# Mezclador2.net
KiCad netlist of a schematic drawn in Altium Designer
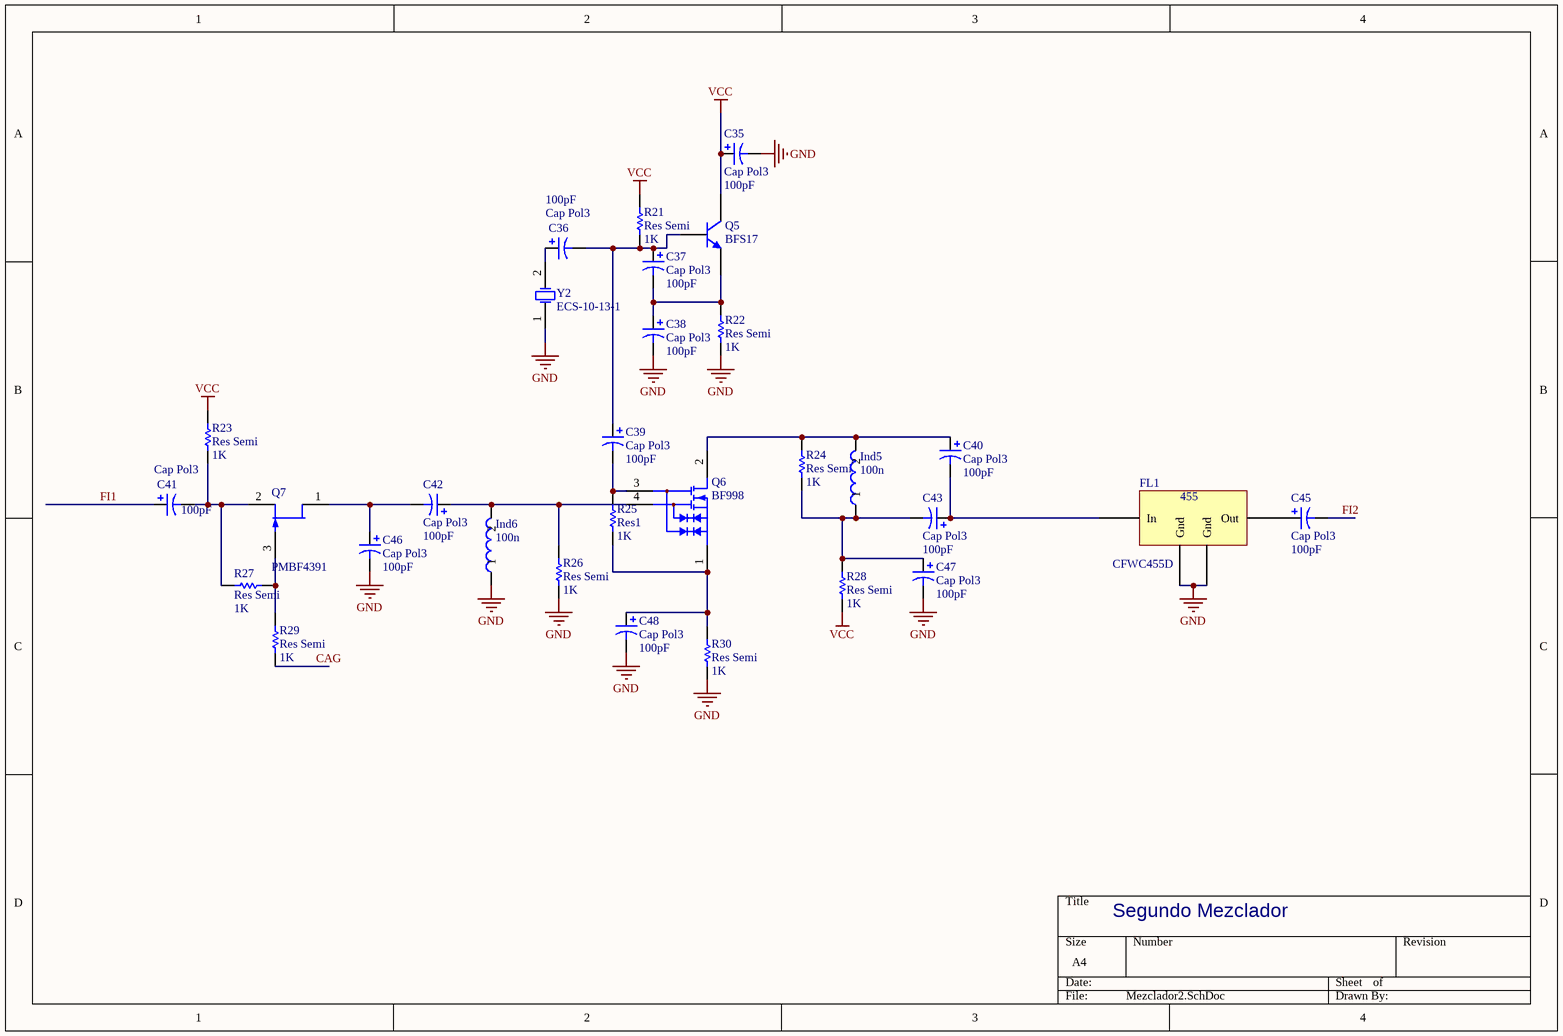
[diagram p0: Mezclador2.SchDoc]

(export (version "E")
  (design (tool "Eeschema 10.0.6"))
  (components
    (comp (ref "C35")
      (value "Cap Pol3")
      (footprint "C0805")
      (description "Polarized Capacitor (Surface Mount)")
      (fields (field (name "ALTIUM_VALUE") "100pF") (field (name "PUBLISHER") "Altium Limited"))
      (libsource (lib "Miscellaneous Devices") (part "Cap Pol3"))
    )
    (comp (ref "C36")
      (value "Cap Pol3")
      (footprint "C0805")
      (description "Polarized Capacitor (Surface Mount)")
      (fields (field (name "ALTIUM_VALUE") "100pF") (field (name "PUBLISHER") "Altium Limited"))
      (libsource (lib "Miscellaneous Devices") (part "Cap Pol3"))
    )
    (comp (ref "C37")
      (value "Cap Pol3")
      (footprint "C0805")
      (description "Polarized Capacitor (Surface Mount)")
      (fields (field (name "ALTIUM_VALUE") "100pF") (field (name "PUBLISHER") "Altium Limited"))
      (libsource (lib "Miscellaneous Devices") (part "Cap Pol3"))
    )
    (comp (ref "C38")
      (value "Cap Pol3")
      (footprint "C0805")
      (description "Polarized Capacitor (Surface Mount)")
      (fields (field (name "ALTIUM_VALUE") "100pF") (field (name "PUBLISHER") "Altium Limited"))
      (libsource (lib "Miscellaneous Devices") (part "Cap Pol3"))
    )
    (comp (ref "C39")
      (value "Cap Pol3")
      (footprint "C0805")
      (description "Polarized Capacitor (Surface Mount)")
      (fields (field (name "ALTIUM_VALUE") "100pF") (field (name "PUBLISHER") "Altium Limited"))
      (libsource (lib "Miscellaneous Devices") (part "Cap Pol3"))
    )
    (comp (ref "C40")
      (value "Cap Pol3")
      (footprint "C0805")
      (description "Polarized Capacitor (Surface Mount)")
      (fields (field (name "ALTIUM_VALUE") "100pF") (field (name "PUBLISHER") "Altium Limited"))
      (libsource (lib "Miscellaneous Devices") (part "Cap Pol3"))
    )
    (comp (ref "C41")
      (value "Cap Pol3")
      (footprint "C0805")
      (description "Polarized Capacitor (Surface Mount)")
      (fields (field (name "ALTIUM_VALUE") "100pF") (field (name "PUBLISHER") "Altium Limited"))
      (libsource (lib "Miscellaneous Devices") (part "Cap Pol3"))
    )
    (comp (ref "C42")
      (value "Cap Pol3")
      (footprint "C0805")
      (description "Polarized Capacitor (Surface Mount)")
      (fields (field (name "ALTIUM_VALUE") "100pF") (field (name "PUBLISHER") "Altium Limited"))
      (libsource (lib "Miscellaneous Devices") (part "Cap Pol3"))
    )
    (comp (ref "C43")
      (value "Cap Pol3")
      (footprint "C0805")
      (description "Polarized Capacitor (Surface Mount)")
      (fields (field (name "ALTIUM_VALUE") "100pF") (field (name "PUBLISHER") "Altium Limited"))
      (libsource (lib "Miscellaneous Devices") (part "Cap Pol3"))
    )
    (comp (ref "C45")
      (value "Cap Pol3")
      (footprint "C0805")
      (description "Polarized Capacitor (Surface Mount)")
      (fields (field (name "ALTIUM_VALUE") "100pF") (field (name "PUBLISHER") "Altium Limited"))
      (libsource (lib "Miscellaneous Devices") (part "Cap Pol3"))
    )
    (comp (ref "C46")
      (value "Cap Pol3")
      (footprint "C0805")
      (description "Polarized Capacitor (Surface Mount)")
      (fields (field (name "ALTIUM_VALUE") "100pF") (field (name "PUBLISHER") "Altium Limited"))
      (libsource (lib "Miscellaneous Devices") (part "Cap Pol3"))
    )
    (comp (ref "C47")
      (value "Cap Pol3")
      (footprint "C0805")
      (description "Polarized Capacitor (Surface Mount)")
      (fields (field (name "ALTIUM_VALUE") "100pF") (field (name "PUBLISHER") "Altium Limited"))
      (libsource (lib "Miscellaneous Devices") (part "Cap Pol3"))
    )
    (comp (ref "C48")
      (value "Cap Pol3")
      (footprint "C0805")
      (description "Polarized Capacitor (Surface Mount)")
      (fields (field (name "ALTIUM_VALUE") "100pF") (field (name "PUBLISHER") "Altium Limited"))
      (libsource (lib "Miscellaneous Devices") (part "Cap Pol3"))
    )
    (comp (ref "FL1")
      (value "CFWC455D")
      (footprint "CFWC455")
      (description "Filtro ceramico")
      (libsource (lib "epf") (part "CFWC455D3"))
    )
    (comp (ref "Ind5")
      (value "Ind2")
      (footprint "AXIAL-0.3")
      (fields (field (name "VALOR") "100n"))
      (libsource (lib "epf") (part "Ind2"))
    )
    (comp (ref "Ind6")
      (value "Ind2")
      (footprint "AXIAL-0.3")
      (fields (field (name "VALOR") "100n"))
      (libsource (lib "epf") (part "Ind2"))
    )
    (comp (ref "Q5")
      (value "BFS17")
      (footprint "SOT-23")
      (description "NPN 1 GHz Wideband Transistor")
      (fields (field (name "PUBLISHER") "Altium Limited"))
      (libsource (lib "Philips Discrete BJT - RF Transistor") (part "BFS17"))
    )
    (comp (ref "Q6")
      (value "BF998")
      (footprint "SOT-143")
      (description "Silicon N-channel Dual-gate MOSFET")
      (fields (field (name "PUBLISHER") "Altium Limited"))
      (libsource (lib "Philips Discrete MOSFET - Low Power") (part "BF998"))
    )
    (comp (ref "Q7")
      (value "PMBF4391")
      (footprint "SOT23_N")
      (description "N-channel Silicon Junction Field-effect Transistor")
      (fields (field (name "PUBLISHER") "Altium Limited"))
      (libsource (lib "Philips Discrete JFET") (part "PMBF4391"))
    )
    (comp (ref "R21")
      (value "Res Semi")
      (footprint "2012[0805]")
      (description "Semiconductor Resistor")
      (fields (field (name "ALTIUM_VALUE") "1K") (field (name "PUBLISHER") "Altium Limited"))
      (libsource (lib "Miscellaneous Devices") (part "Res Semi"))
    )
    (comp (ref "R22")
      (value "Res Semi")
      (footprint "2012[0805]")
      (description "Semiconductor Resistor")
      (fields (field (name "ALTIUM_VALUE") "1K") (field (name "PUBLISHER") "Altium Limited"))
      (libsource (lib "Miscellaneous Devices") (part "Res Semi"))
    )
    (comp (ref "R23")
      (value "Res Semi")
      (footprint "2012[0805]")
      (description "Semiconductor Resistor")
      (fields (field (name "ALTIUM_VALUE") "1K") (field (name "PUBLISHER") "Altium Limited"))
      (libsource (lib "Miscellaneous Devices") (part "Res Semi"))
    )
    (comp (ref "R24")
      (value "Res Semi")
      (footprint "2012[0805]")
      (description "Semiconductor Resistor")
      (fields (field (name "ALTIUM_VALUE") "1K") (field (name "PUBLISHER") "Altium Limited"))
      (libsource (lib "Miscellaneous Devices") (part "Res Semi"))
    )
    (comp (ref "R25")
      (value "Res1")
      (footprint "AXIAL-0.3")
      (description "Resistor")
      (fields (field (name "ALTIUM_VALUE") "1K") (field (name "PUBLISHER") "Altium Limited"))
      (libsource (lib "Miscellaneous Devices") (part "Res1"))
    )
    (comp (ref "R26")
      (value "Res Semi")
      (footprint "2012[0805]")
      (description "Semiconductor Resistor")
      (fields (field (name "ALTIUM_VALUE") "1K") (field (name "PUBLISHER") "Altium Limited"))
      (libsource (lib "Miscellaneous Devices") (part "Res Semi"))
    )
    (comp (ref "R27")
      (value "Res Semi")
      (footprint "2012[0805]")
      (description "Semiconductor Resistor")
      (fields (field (name "ALTIUM_VALUE") "1K") (field (name "PUBLISHER") "Altium Limited"))
      (libsource (lib "Miscellaneous Devices") (part "Res Semi"))
    )
    (comp (ref "R28")
      (value "Res Semi")
      (footprint "2012[0805]")
      (description "Semiconductor Resistor")
      (fields (field (name "ALTIUM_VALUE") "1K") (field (name "PUBLISHER") "Altium Limited"))
      (libsource (lib "Miscellaneous Devices") (part "Res Semi"))
    )
    (comp (ref "R29")
      (value "Res Semi")
      (footprint "2012[0805]")
      (description "Semiconductor Resistor")
      (fields (field (name "ALTIUM_VALUE") "1K") (field (name "PUBLISHER") "Altium Limited"))
      (libsource (lib "Miscellaneous Devices") (part "Res Semi"))
    )
    (comp (ref "R30")
      (value "Res Semi")
      (footprint "2012[0805]")
      (description "Semiconductor Resistor")
      (fields (field (name "ALTIUM_VALUE") "1K") (field (name "PUBLISHER") "Altium Limited"))
      (libsource (lib "Miscellaneous Devices") (part "Res Semi"))
    )
    (comp (ref "Y2")
      (value "ECS-10-13-1")
      (footprint "HC-49U")
      (description "Crystal Oscillator")
      (fields (field (name "PUBLISHER") "Altium Limited"))
      (libsource (lib "ECS Crystal Oscillator") (part "ECS-10-13-1"))
    )
  )
  (nets
    (net (code "1") (name "/CAG") (class "Default")
      (node (ref "R29") (pin "2") (pinfunction "2_2") (pintype "passive"))
    )
    (net (code "2") (name "/FI1") (class "Default")
      (node (ref "C41") (pin "1") (pinfunction "1_1") (pintype "passive"))
    )
    (net (code "3") (name "/FI2") (class "Default")
      (node (ref "C45") (pin "2") (pinfunction "2_2") (pintype "passive"))
    )
    (net (code "4") (name "GND") (class "Default")
      (node (ref "C35") (pin "2") (pinfunction "2_2") (pintype "passive"))
      (node (ref "C38") (pin "2") (pinfunction "2_2") (pintype "passive"))
      (node (ref "C46") (pin "2") (pinfunction "2_2") (pintype "passive"))
      (node (ref "C47") (pin "2") (pinfunction "2_2") (pintype "passive"))
      (node (ref "C48") (pin "2") (pinfunction "2_2") (pintype "passive"))
      (node (ref "FL1") (pin "3") (pinfunction "Gnd_3") (pintype "passive"))
      (node (ref "FL1") (pin "4") (pinfunction "Gnd_4") (pintype "passive"))
      (node (ref "Ind6") (pin "1") (pinfunction "1_1") (pintype "passive"))
      (node (ref "R22") (pin "1") (pinfunction "1_1") (pintype "passive"))
      (node (ref "R26") (pin "1") (pinfunction "1_1") (pintype "passive"))
      (node (ref "R30") (pin "1") (pinfunction "1_1") (pintype "passive"))
      (node (ref "Y2") (pin "1") (pinfunction "OSC1_1") (pintype "passive"))
    )
    (net (code "5") (name "Net-(C43-Pad2)") (class "Default")
      (node (ref "C43") (pin "2") (pinfunction "2_2") (pintype "passive"))
      (node (ref "C47") (pin "1") (pinfunction "1_1") (pintype "passive"))
      (node (ref "Ind5") (pin "1") (pinfunction "1_1") (pintype "passive"))
      (node (ref "R24") (pin "1") (pinfunction "1_1") (pintype "passive"))
      (node (ref "R28") (pin "2") (pinfunction "2_2") (pintype "passive"))
    )
    (net (code "6") (name "Net-(FL1-In)") (class "Default")
      (node (ref "C40") (pin "2") (pinfunction "2_2") (pintype "passive"))
      (node (ref "C43") (pin "1") (pinfunction "1_1") (pintype "passive"))
      (node (ref "FL1") (pin "1") (pinfunction "In_1") (pintype "passive"))
    )
    (net (code "7") (name "Net-(FL1-Out)") (class "Default")
      (node (ref "C45") (pin "1") (pinfunction "1_1") (pintype "passive"))
      (node (ref "FL1") (pin "2") (pinfunction "Out_2") (pintype "passive"))
    )
    (net (code "8") (name "Net-(Q5-B)") (class "Default")
      (node (ref "C36") (pin "2") (pinfunction "2_2") (pintype "passive"))
      (node (ref "C37") (pin "1") (pinfunction "1_1") (pintype "passive"))
      (node (ref "C39") (pin "1") (pinfunction "1_1") (pintype "passive"))
      (node (ref "Q5") (pin "1") (pinfunction "B_1") (pintype "passive"))
      (node (ref "R21") (pin "1") (pinfunction "1_1") (pintype "passive"))
    )
    (net (code "9") (name "Net-(Q5-E)") (class "Default")
      (node (ref "C37") (pin "2") (pinfunction "2_2") (pintype "passive"))
      (node (ref "C38") (pin "1") (pinfunction "1_1") (pintype "passive"))
      (node (ref "Q5") (pin "2") (pinfunction "E_2") (pintype "passive"))
      (node (ref "R22") (pin "2") (pinfunction "2_2") (pintype "passive"))
    )
    (net (code "10") (name "Net-(Q6-D)") (class "Default")
      (node (ref "C40") (pin "1") (pinfunction "1_1") (pintype "passive"))
      (node (ref "Ind5") (pin "2") (pinfunction "2_2") (pintype "passive"))
      (node (ref "Q6") (pin "2") (pinfunction "D_2") (pintype "passive"))
      (node (ref "R24") (pin "2") (pinfunction "2_2") (pintype "passive"))
    )
    (net (code "11") (name "Net-(Q6-G1)") (class "Default")
      (node (ref "C42") (pin "1") (pinfunction "1_1") (pintype "passive"))
      (node (ref "Ind6") (pin "2") (pinfunction "2_2") (pintype "passive"))
      (node (ref "Q6") (pin "4") (pinfunction "G1_4") (pintype "passive"))
      (node (ref "R26") (pin "2") (pinfunction "2_2") (pintype "passive"))
    )
    (net (code "12") (name "Net-(Q6-G2)") (class "Default")
      (node (ref "C39") (pin "2") (pinfunction "2_2") (pintype "passive"))
      (node (ref "Q6") (pin "3") (pinfunction "G2_3") (pintype "passive"))
      (node (ref "R25") (pin "2") (pinfunction "2_2") (pintype "passive"))
    )
    (net (code "13") (name "Net-(Q6-S)") (class "Default")
      (node (ref "C48") (pin "1") (pinfunction "1_1") (pintype "passive"))
      (node (ref "Q6") (pin "1") (pinfunction "S_1") (pintype "passive"))
      (node (ref "R25") (pin "1") (pinfunction "1_1") (pintype "passive"))
      (node (ref "R30") (pin "2") (pinfunction "2_2") (pintype "passive"))
    )
    (net (code "14") (name "Net-(Q7-D)") (class "Default")
      (node (ref "C42") (pin "2") (pinfunction "2_2") (pintype "passive"))
      (node (ref "C46") (pin "1") (pinfunction "1_1") (pintype "passive"))
      (node (ref "Q7") (pin "1") (pinfunction "D_1") (pintype "passive"))
    )
    (net (code "15") (name "Net-(Q7-G)") (class "Default")
      (node (ref "Q7") (pin "3") (pinfunction "G_3") (pintype "passive"))
      (node (ref "R27") (pin "2") (pinfunction "2_2") (pintype "passive"))
      (node (ref "R29") (pin "1") (pinfunction "1_1") (pintype "passive"))
    )
    (net (code "16") (name "Net-(Q7-S)") (class "Default")
      (node (ref "C41") (pin "2") (pinfunction "2_2") (pintype "passive"))
      (node (ref "Q7") (pin "2") (pinfunction "S_2") (pintype "passive"))
      (node (ref "R23") (pin "1") (pinfunction "1_1") (pintype "passive"))
      (node (ref "R27") (pin "1") (pinfunction "1_1") (pintype "passive"))
    )
    (net (code "17") (name "Net-(Y2-OSC2)") (class "Default")
      (node (ref "C36") (pin "1") (pinfunction "1_1") (pintype "passive"))
      (node (ref "Y2") (pin "2") (pinfunction "OSC2_2") (pintype "passive"))
    )
    (net (code "18") (name "VCC") (class "Default")
      (node (ref "C35") (pin "1") (pinfunction "1_1") (pintype "passive"))
      (node (ref "Q5") (pin "3") (pinfunction "C_3") (pintype "passive"))
      (node (ref "R21") (pin "2") (pinfunction "2_2") (pintype "passive"))
      (node (ref "R23") (pin "2") (pinfunction "2_2") (pintype "passive"))
      (node (ref "R28") (pin "1") (pinfunction "1_1") (pintype "passive"))
    )
  )
)
